# POWER.net
KiCad netlist of a schematic drawn in Altium Designer
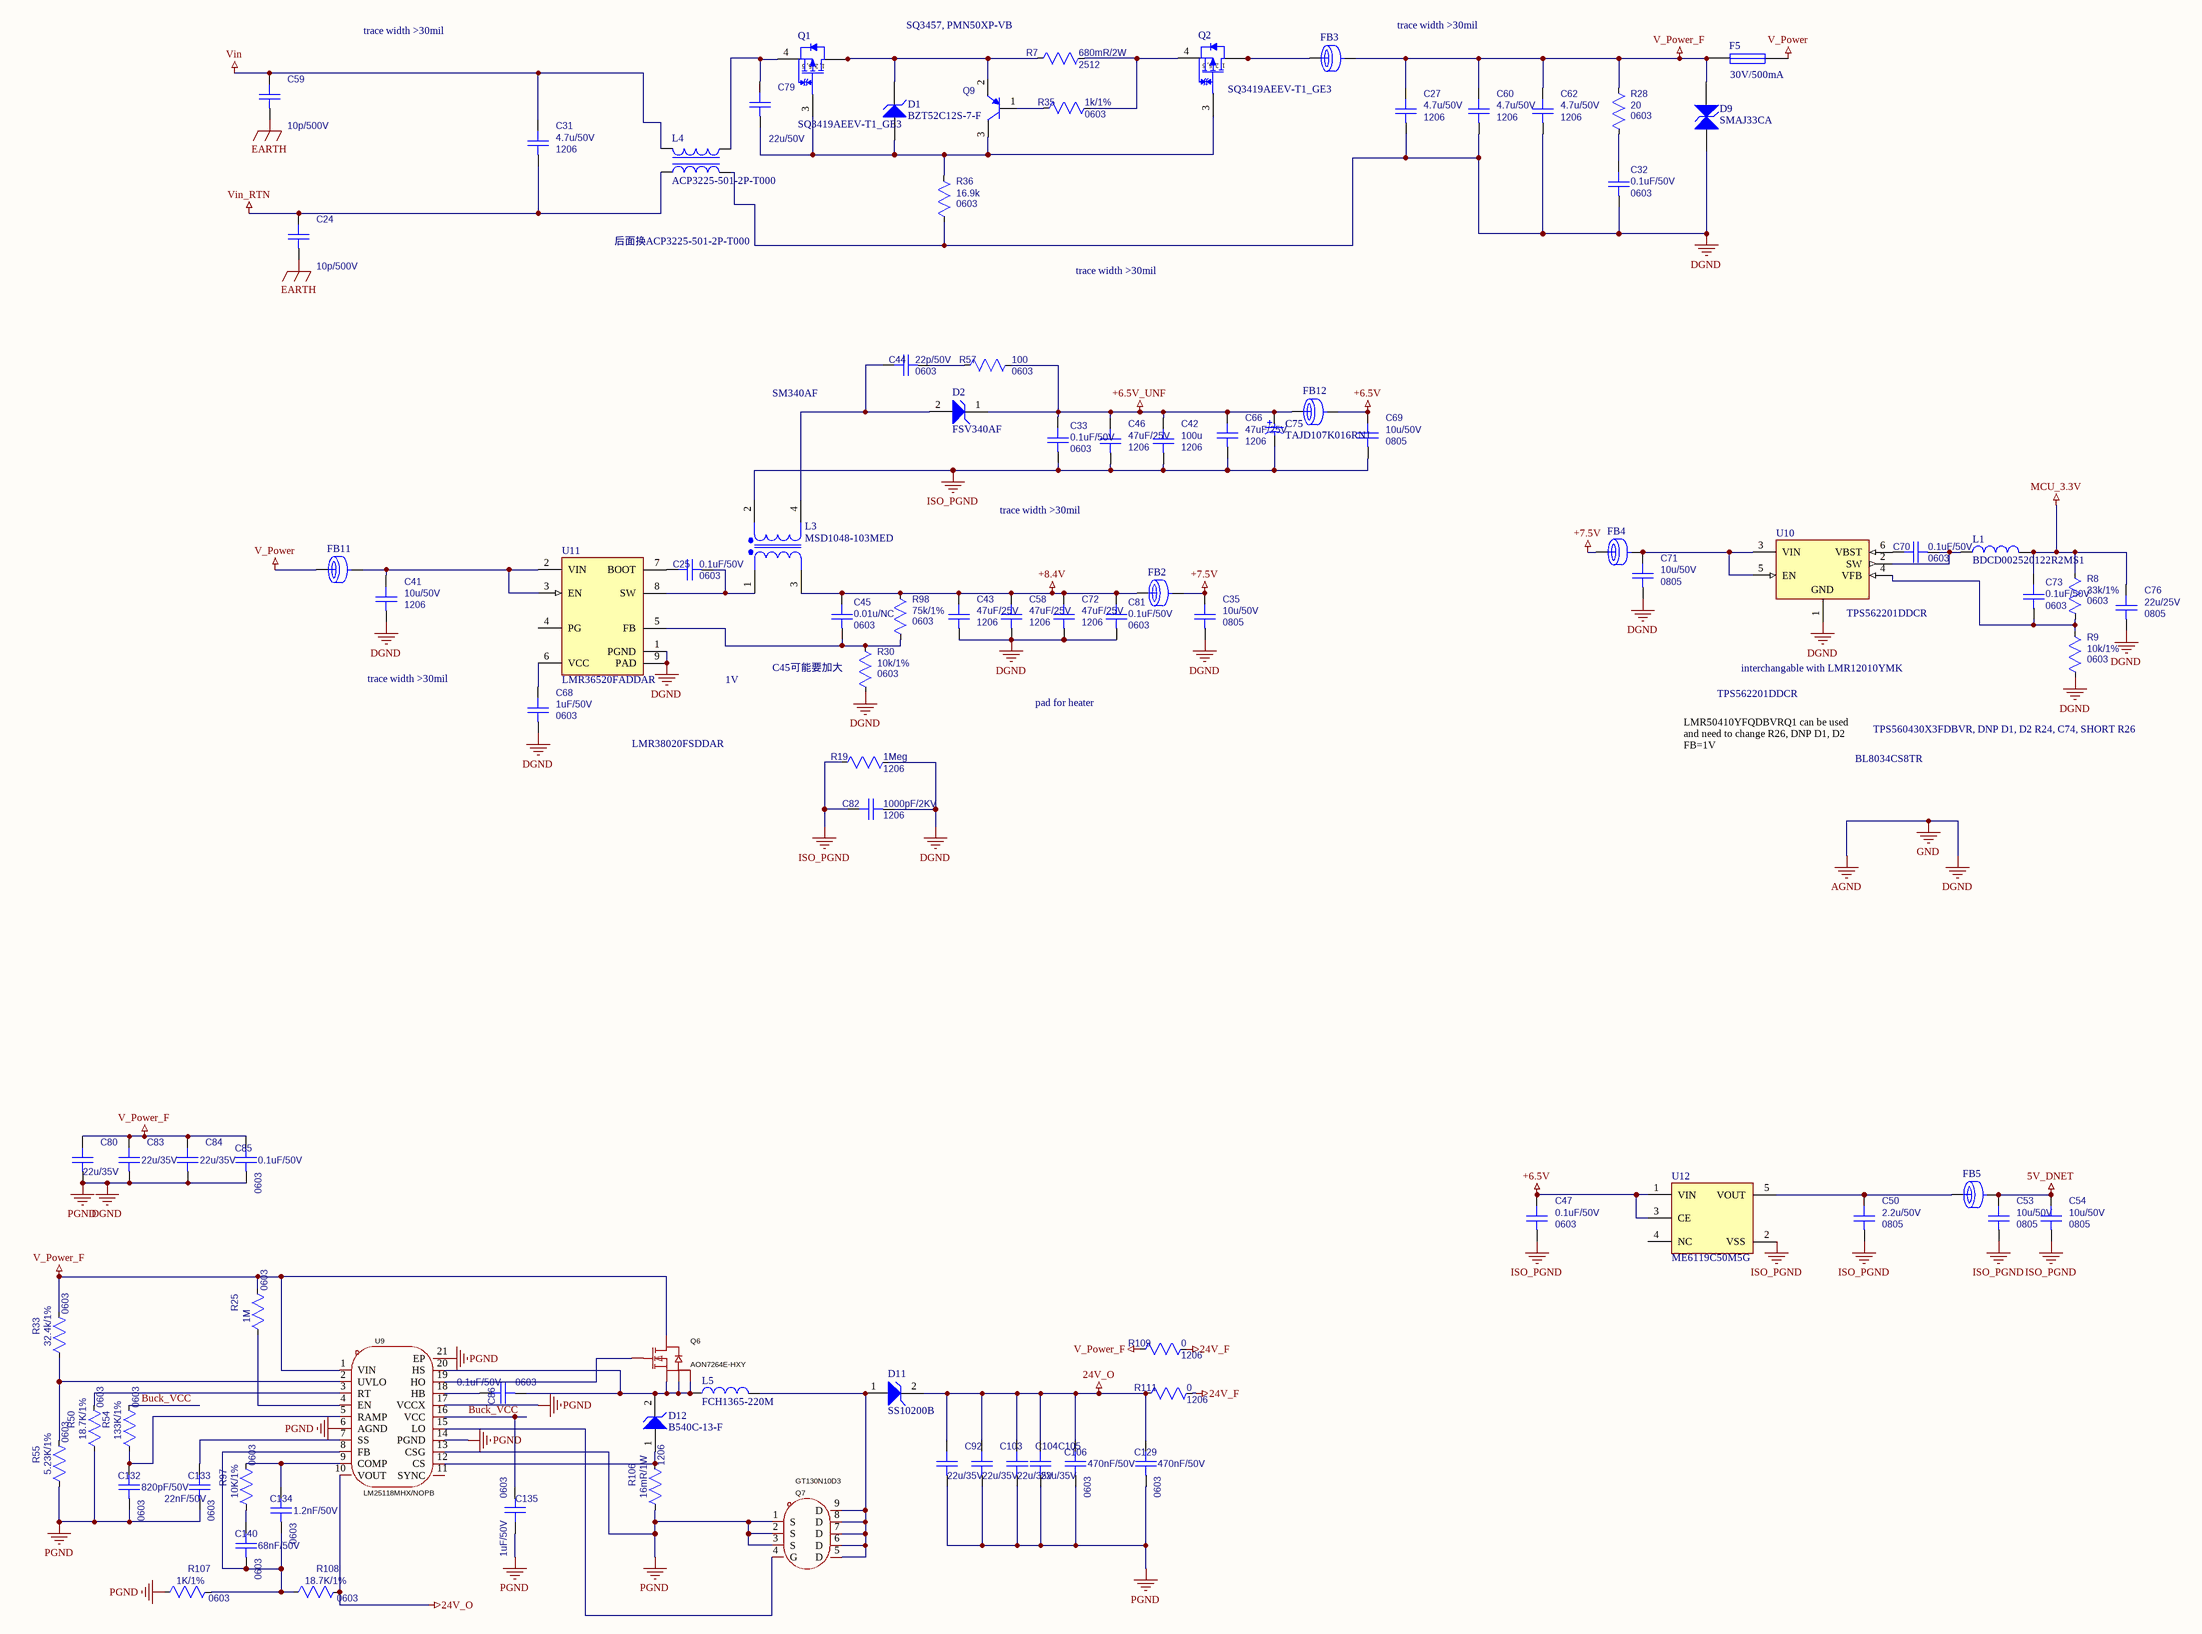
[diagram p0: POWER.SchDoc]

(export (version "E")
  (design (tool "Eeschema 10.0.6"))
  (components
    (comp (ref "C24")
      (value "10p/500V")
      (footprint "CAPC2012X127N_0805")
      (fields (field (name "PARTNUMBER") "CC0805JRNPOBBN100") (field (name "TOLERANCE") "[tol]"))
      (libsource (lib "Karl") (part "Capacitor_0805"))
    )
    (comp (ref "C25")
      (value "0.1uF/50V")
      (footprint "CAPC1608X092N_0603")
      (fields
        (field (name "PARTNUMBER") "CC0603KRX7R9BB104")
        (field (name "TOLERANCE") "[tol]")
        (field (name "PACKAGE") "0603")
      )
      (libsource (lib "Karl") (part "Capacitor_0603"))
    )
    (comp (ref "C27")
      (value "4.7u/50V")
      (footprint "CAPC3216X156N_1206")
      (fields
        (field (name "PARTNUMBER") "CL31B475KBHNNNE")
        (field (name "TOLERANCE") "[tol]")
        (field (name "PACKAGE") "1206")
      )
      (libsource (lib "Karl") (part "Capacitor_1206"))
    )
    (comp (ref "C31")
      (value "4.7u/50V")
      (footprint "CAPC3216X156N_1206")
      (fields
        (field (name "PARTNUMBER") "CL31B475KBHNNNE")
        (field (name "TOLERANCE") "[tol]")
        (field (name "PACKAGE") "1206")
      )
      (libsource (lib "Karl") (part "Capacitor_1206"))
    )
    (comp (ref "C32")
      (value "0.1uF/50V")
      (footprint "CAPC1608X092N_0603")
      (fields
        (field (name "PARTNUMBER") "CC0603KRX7R9BB104")
        (field (name "TOLERANCE") "[tol]")
        (field (name "PACKAGE") "0603")
      )
      (libsource (lib "Karl") (part "Capacitor_0603"))
    )
    (comp (ref "C33")
      (value "0.1uF/50V")
      (footprint "CAPC1608X092N_0603")
      (fields
        (field (name "PARTNUMBER") "CC0603KRX7R9BB104")
        (field (name "TOLERANCE") "[tol]")
        (field (name "PACKAGE") "0603")
      )
      (libsource (lib "Karl") (part "Capacitor_0603"))
    )
    (comp (ref "C35")
      (value "10u/50V")
      (footprint "CAPC2012X127N_0805")
      (fields
        (field (name "PARTNUMBER") "CL21A106KBYQNNE")
        (field (name "TOLERANCE") "[tol]")
        (field (name "PACKAGE") "0805")
      )
      (libsource (lib "Karl") (part "Capacitor_0805"))
    )
    (comp (ref "C41")
      (value "10u/50V")
      (footprint "CAPC3216X156N_1206")
      (fields
        (field (name "PARTNUMBER") "CL31A106KBHNNNE")
        (field (name "TOLERANCE") "[tol]")
        (field (name "PACKAGE") "1206")
      )
      (libsource (lib "Karl") (part "Capacitor_1206"))
    )
    (comp (ref "C42")
      (value "100u")
      (footprint "CAPC3216X156N_1206")
      (fields
        (field (name "PARTNUMBER") "GRM31CR61A107MEA8L")
        (field (name "TOLERANCE") "[tol]")
        (field (name "PACKAGE") "1206")
      )
      (libsource (lib "Karl") (part "Capacitor_1206"))
    )
    (comp (ref "C43")
      (value "47uF/25V")
      (footprint "CAPC3216X156N_1206")
      (fields
        (field (name "PARTNUMBER") "GRM31CR61E476ME44L")
        (field (name "TOLERANCE") "[tol]")
        (field (name "PACKAGE") "1206")
      )
      (libsource (lib "Karl") (part "Capacitor_1206"))
    )
    (comp (ref "C44")
      (value "22p/50V")
      (footprint "CAPC1608X092N_0603")
      (fields
        (field (name "PARTNUMBER") "C0603C220J1GACTU")
        (field (name "TOLERANCE") "[tol]")
        (field (name "PACKAGE") "0603")
      )
      (libsource (lib "Karl") (part "Capacitor_0603"))
    )
    (comp (ref "C45")
      (value "0.01u/NC")
      (footprint "CAPC1608X092N_0603")
      (fields
        (field (name "PARTNUMBER") "0603B103K500NT")
        (field (name "TOLERANCE") "[tol]")
        (field (name "PACKAGE") "0603")
        (field (name "Comment") "0.01uF/50V")
      )
      (libsource (lib "Karl") (part "Capacitor_0603"))
    )
    (comp (ref "C46")
      (value "47uF/25V")
      (footprint "CAPC3216X156N_1206")
      (fields
        (field (name "PARTNUMBER") "GRM31CR61E476ME44L")
        (field (name "TOLERANCE") "[tol]")
        (field (name "PACKAGE") "1206")
      )
      (libsource (lib "Karl") (part "Capacitor_1206"))
    )
    (comp (ref "C47")
      (value "0.1uF/50V")
      (footprint "CAPC1608X092N_0603")
      (fields
        (field (name "PARTNUMBER") "CC0603KRX7R9BB104")
        (field (name "TOLERANCE") "[tol]")
        (field (name "PACKAGE") "0603")
      )
      (libsource (lib "Karl") (part "Capacitor_0603"))
    )
    (comp (ref "C50")
      (value "2.2u/50V")
      (footprint "CAPC2012X127N_0805")
      (fields
        (field (name "PARTNUMBER") "CC0805KKX7R9BB225")
        (field (name "TOLERANCE") "[tol]")
        (field (name "PACKAGE") "0805")
      )
      (libsource (lib "Karl") (part "Capacitor_0805"))
    )
    (comp (ref "C53")
      (value "10u/50V")
      (footprint "CAPC2012X127N_0805")
      (fields
        (field (name "PARTNUMBER") "CL21A106KBYQNNE")
        (field (name "TOLERANCE") "[tol]")
        (field (name "PACKAGE") "0805")
      )
      (libsource (lib "Karl") (part "Capacitor_0805"))
    )
    (comp (ref "C54")
      (value "10u/50V")
      (footprint "CAPC2012X127N_0805")
      (fields
        (field (name "PARTNUMBER") "CL21A106KBYQNNE")
        (field (name "TOLERANCE") "[tol]")
        (field (name "PACKAGE") "0805")
      )
      (libsource (lib "Karl") (part "Capacitor_0805"))
    )
    (comp (ref "C58")
      (value "47uF/25V")
      (footprint "CAPC3216X156N_1206")
      (fields
        (field (name "PARTNUMBER") "GRM31CR61E476ME44L")
        (field (name "TOLERANCE") "[tol]")
        (field (name "PACKAGE") "1206")
      )
      (libsource (lib "Karl") (part "Capacitor_1206"))
    )
    (comp (ref "C59")
      (value "10p/500V")
      (footprint "CAPC2012X127N_0805")
      (fields (field (name "PARTNUMBER") "CC0805JRNPOBBN100") (field (name "TOLERANCE") "[tol]"))
      (libsource (lib "Karl") (part "Capacitor_0805"))
    )
    (comp (ref "C60")
      (value "4.7u/50V")
      (footprint "CAPC3216X156N_1206")
      (fields
        (field (name "PARTNUMBER") "CL31B475KBHNNNE")
        (field (name "TOLERANCE") "[tol]")
        (field (name "PACKAGE") "1206")
      )
      (libsource (lib "Karl") (part "Capacitor_1206"))
    )
    (comp (ref "C62")
      (value "4.7u/50V")
      (footprint "CAPC3216X156N_1206")
      (fields
        (field (name "PARTNUMBER") "CL31B475KBHNNNE")
        (field (name "TOLERANCE") "[tol]")
        (field (name "PACKAGE") "1206")
      )
      (libsource (lib "Karl") (part "Capacitor_1206"))
    )
    (comp (ref "C66")
      (value "47uF/25V")
      (footprint "CAPC3216X156N_1206")
      (fields
        (field (name "PARTNUMBER") "GRM31CR61E476ME44L")
        (field (name "TOLERANCE") "[tol]")
        (field (name "PACKAGE") "1206")
      )
      (libsource (lib "Karl") (part "Capacitor_1206"))
    )
    (comp (ref "C68")
      (value "1uF/50V")
      (footprint "CAPC1608X092N_0603")
      (fields
        (field (name "PARTNUMBER") "CL10A105KB8NNNC")
        (field (name "TOLERANCE") "[tol]")
        (field (name "PACKAGE") "0603")
      )
      (libsource (lib "Karl") (part "Capacitor_0603"))
    )
    (comp (ref "C69")
      (value "10u/50V")
      (footprint "CAPC2012X127N_0805")
      (fields
        (field (name "PARTNUMBER") "CL21A106KBYQNNE")
        (field (name "TOLERANCE") "[tol]")
        (field (name "PACKAGE") "0805")
      )
      (libsource (lib "Karl") (part "Capacitor_0805"))
    )
    (comp (ref "C70")
      (value "0.1uF/50V")
      (footprint "CAPC1608X092N_0603")
      (fields
        (field (name "PARTNUMBER") "CC0603KRX7R9BB104")
        (field (name "TOLERANCE") "[tol]")
        (field (name "PACKAGE") "0603")
      )
      (libsource (lib "Karl") (part "Capacitor_0603"))
    )
    (comp (ref "C71")
      (value "10u/50V")
      (footprint "CAPC2012X127N_0805")
      (fields
        (field (name "PARTNUMBER") "CL21A106KBYQNNE")
        (field (name "TOLERANCE") "[tol]")
        (field (name "PACKAGE") "0805")
      )
      (libsource (lib "Karl") (part "Capacitor_0805"))
    )
    (comp (ref "C72")
      (value "47uF/25V")
      (footprint "CAPC3216X156N_1206")
      (fields
        (field (name "PARTNUMBER") "GRM31CR61E476ME44L")
        (field (name "TOLERANCE") "[tol]")
        (field (name "PACKAGE") "1206")
      )
      (libsource (lib "Karl") (part "Capacitor_1206"))
    )
    (comp (ref "C73")
      (value "0.1uF/50V")
      (footprint "CAPC1608X092N_0603")
      (fields (field (name "TOLERANCE") "[tol]") (field (name "PACKAGE") "0603"))
      (libsource (lib "Karl") (part "Capacitor_0603"))
    )
    (comp (ref "C75")
      (value "TAJD107K016RNJ")
      (footprint "AVX-TAJ-D-2_L")
      (fields (field (name "TOLERANCE") "±10%") (field (name "PUBLISHER") "Bolgen Studio"))
      (libsource (lib "Bogen") (part "TAJD107K016RNJ"))
    )
    (comp (ref "C76")
      (value "22u/25V")
      (footprint "CAPC2012X127N_0805")
      (fields
        (field (name "PARTNUMBER") "CL21A226MAYNNNE")
        (field (name "TOLERANCE") "[tol]")
        (field (name "PACKAGE") "0805")
      )
      (libsource (lib "Karl") (part "Capacitor_0805"))
    )
    (comp (ref "C79")
      (value "22u/50V")
      (footprint "2220c")
      (description "Capacitor, MLCC")
      (fields (field (name "MANUFACTURER") "KEMET") (field (name "PARTNUMBER") "FS55X226K500EHG"))
      (libsource (lib "Karl") (part "Capacitor_1206"))
    )
    (comp (ref "C80")
      (value "22u/35V")
      (footprint "CAPC3216X156N_1206")
      (description "Capacitor, MLCC")
      (fields (field (name "MANUFACTURER") "KEMET") (field (name "PARTNUMBER") "C3216X5R1V226MTJ00E"))
      (libsource (lib "Karl") (part "Capacitor_1206"))
    )
    (comp (ref "C81")
      (value "0.1uF/50V")
      (footprint "CAPC1608X092N_0603")
      (fields
        (field (name "PARTNUMBER") "CC0603KRX7R9BB104")
        (field (name "TOLERANCE") "[tol]")
        (field (name "PACKAGE") "0603")
      )
      (libsource (lib "Karl") (part "Capacitor_0603"))
    )
    (comp (ref "C82")
      (value "1000pF/2KV")
      (footprint "CAPC3216X156N_1206")
      (fields
        (field (name "PARTNUMBER") "CC1206KKX7RDBB102")
        (field (name "TOLERANCE") "[tol]")
        (field (name "PACKAGE") "1206")
      )
      (libsource (lib "Karl") (part "Capacitor_1206"))
    )
    (comp (ref "C83")
      (value "22u/35V")
      (footprint "CAPC3216X156N_1206")
      (description "Capacitor, MLCC")
      (fields (field (name "MANUFACTURER") "KEMET") (field (name "PARTNUMBER") "C3216X5R1V226MTJ00E"))
      (libsource (lib "Karl") (part "Capacitor_1206"))
    )
    (comp (ref "C84")
      (value "22u/35V")
      (footprint "CAPC3216X156N_1206")
      (description "Capacitor, MLCC")
      (fields (field (name "MANUFACTURER") "KEMET") (field (name "PARTNUMBER") "C3216X5R1V226MTJ00E"))
      (libsource (lib "Karl") (part "Capacitor_1206"))
    )
    (comp (ref "C85")
      (value "0.1uF/50V")
      (footprint "CAPC1608X092N_0603")
      (description "Capacitor, MLCC")
      (fields
        (field (name "MANUFACTURER") "KEMET")
        (field (name "PARTNUMBER") "CC0603KRX7R9BB104")
        (field (name "PACKAGE") "0603")
      )
      (libsource (lib "Karl") (part "Capacitor_0603"))
    )
    (comp (ref "C86")
      (value "0.1uF/50V")
      (footprint "CAPC1608X092N_0603")
      (description "Capacitor, MLCC")
      (fields
        (field (name "MANUFACTURER") "KEMET")
        (field (name "PARTNUMBER") "CC0603KRX7R9BB104")
        (field (name "PACKAGE") "0603")
      )
      (libsource (lib "Karl") (part "Capacitor_0603"))
    )
    (comp (ref "C92")
      (value "22u/35V")
      (footprint "CAPC3216X156N_1206")
      (description "Capacitor, MLCC")
      (fields (field (name "MANUFACTURER") "KEMET") (field (name "PARTNUMBER") "C3216X5R1V226MTJ00E"))
      (libsource (lib "Karl") (part "Capacitor_1206"))
    )
    (comp (ref "C103")
      (value "22u/35V")
      (footprint "CAPC3216X156N_1206")
      (description "Capacitor, MLCC")
      (fields (field (name "MANUFACTURER") "KEMET") (field (name "PARTNUMBER") "C3216X5R1V226MTJ00E"))
      (libsource (lib "Karl") (part "Capacitor_1206"))
    )
    (comp (ref "C104")
      (value "22u/35V")
      (footprint "CAPC3216X156N_1206")
      (description "Capacitor, MLCC")
      (fields (field (name "MANUFACTURER") "KEMET") (field (name "PARTNUMBER") "C3216X5R1V226MTJ00E"))
      (libsource (lib "Karl") (part "Capacitor_1206"))
    )
    (comp (ref "C105")
      (value "22u/35V")
      (footprint "CAPC3216X156N_1206")
      (description "Capacitor, MLCC")
      (fields (field (name "MANUFACTURER") "KEMET") (field (name "PARTNUMBER") "C3216X5R1V226MTJ00E"))
      (libsource (lib "Karl") (part "Capacitor_1206"))
    )
    (comp (ref "C106")
      (value "470nF/50V")
      (footprint "CAPC1608X092N_0603")
      (description "Capacitor, MLCC")
      (fields (field (name "MANUFACTURER") "KEMET") (field (name "PACKAGE") "0603"))
      (libsource (lib "Karl") (part "Capacitor_0603"))
    )
    (comp (ref "C129")
      (value "470nF/50V")
      (footprint "CAPC1608X092N_0603")
      (description "Capacitor, MLCC")
      (fields (field (name "MANUFACTURER") "KEMET") (field (name "PACKAGE") "0603"))
      (libsource (lib "Karl") (part "Capacitor_0603"))
    )
    (comp (ref "C132")
      (value "820pF/50V")
      (footprint "CAPC1608X092N_0603")
      (description "Capacitor, MLCC")
      (fields (field (name "MANUFACTURER") "KEMET") (field (name "PACKAGE") "0603"))
      (libsource (lib "Karl") (part "Capacitor_0603"))
    )
    (comp (ref "C133")
      (value "22nF/50V")
      (footprint "CAPC1608X092N_0603")
      (description "Capacitor, MLCC")
      (fields (field (name "MANUFACTURER") "KEMET") (field (name "PACKAGE") "0603"))
      (libsource (lib "Karl") (part "Capacitor_0603"))
    )
    (comp (ref "C134")
      (value "1.2nF/50V")
      (footprint "CAPC1608X092N_0603")
      (description "Capacitor, MLCC")
      (fields (field (name "MANUFACTURER") "KEMET") (field (name "PACKAGE") "0603"))
      (libsource (lib "Karl") (part "Capacitor_0603"))
    )
    (comp (ref "C135")
      (value "1uF/50V")
      (footprint "CAPC1608X092N_0603")
      (description "Capacitor, MLCC")
      (fields
        (field (name "MANUFACTURER") "KEMET")
        (field (name "PARTNUMBER") "CL10A105KB8NNNC")
        (field (name "PACKAGE") "0603")
      )
      (libsource (lib "Karl") (part "Capacitor_0603"))
    )
    (comp (ref "C140")
      (value "68nF/50V")
      (footprint "CAPC1608X092N_0603")
      (description "Capacitor, MLCC")
      (fields (field (name "MANUFACTURER") "KEMET") (field (name "PACKAGE") "0603"))
      (libsource (lib "Karl") (part "Capacitor_0603"))
    )
    (comp (ref "D1")
      (value "BZT52C12S-7-F")
      (footprint "DIOD-SOD323-2_V")
      (fields (field (name "PARTNUMBER") "BZT52C12S"))
      (libsource (lib "Bogen") (part "BZT52C12S-7-F"))
    )
    (comp (ref "D2")
      (value "FSV340AF")
      (footprint "ONSC-SMA-FL-2-403AD_V")
      (fields (field (name "PARTNUMBER") "SM340AF"))
      (libsource (lib "") (part "FSV340AF_1"))
    )
    (comp (ref "D9")
      (value "SMAJ33CA")
      (footprint "LFUS-DO-214AC-A-2_N")
      (libsource (lib "Bogen") (part "SMAJ12CA"))
    )
    (comp (ref "D11")
      (value "SS10200B")
      (footprint "SMB")
      (description "Schottky Barrier Rectifier, 40 V, 2-Pin SMA-FL, Pb-Free, Tape and Reel")
      (fields (field (name "MANUFACTURER") "On Semiconductor"))
      (libsource (lib "Bogen") (part "FSV340AF"))
    )
    (comp (ref "D12")
      (value "B540C-13-F")
      (footprint "SMC")
      (description "Schottky Barrier Rectifier, 40 V, 2-Pin SMA-FL, Pb-Free, Tape and Reel")
      (fields (field (name "MANUFACTURER") "On Semiconductor"))
      (libsource (lib "Bogen") (part "FSV340AF"))
    )
    (comp (ref "F5")
      (value "30V/500mA")
      (footprint "RESC3216X070N_1206")
      (fields (field (name "PARTNUMBER") "BSMD1206-050-30V") (field (name "PUBLISHER") "Altium Limited"))
      (libsource (lib "Miscellaneous Devices") (part "Fuse 1"))
    )
    (comp (ref "FB2")
      (value "FBC0603")
      (footprint "FBC0603")
      (fields (field (name "PARTNUMBER") "BLM18AG601SN1D"))
      (libsource (lib "Karl") (part "FBC0603"))
    )
    (comp (ref "FB3")
      (value "BLM31PG121SN1L")
      (footprint "RESC3216X070N_1206")
      (libsource (lib "Karl") (part "FBC0603"))
    )
    (comp (ref "FB4")
      (value "FBC0603")
      (footprint "FBC0603")
      (fields (field (name "PARTNUMBER") "BLM18AG601SN1D"))
      (libsource (lib "Karl") (part "FBC0603"))
    )
    (comp (ref "FB5")
      (value "FBC0603")
      (footprint "FBC0603")
      (fields (field (name "PARTNUMBER") "BLM18AG601SN1D"))
      (libsource (lib "Karl") (part "FBC0603"))
    )
    (comp (ref "FB11")
      (value "FBC0603")
      (footprint "FBC0603")
      (fields (field (name "PARTNUMBER") "BLM18AG601SN1D"))
      (libsource (lib "Karl") (part "FBC0603"))
    )
    (comp (ref "FB12")
      (value "FBC0603")
      (footprint "FBC0603")
      (fields (field (name "PARTNUMBER") "BLM18AG601SN1D"))
      (libsource (lib "Karl") (part "FBC0603"))
    )
    (comp (ref "L1")
      (value "BDCD002520122R2MS1")
      (footprint "PULS-BDCD00252012_V")
      (fields (field (name "TOLERANCE") "±20%"))
      (libsource (lib "Bogen") (part "BDCD002520122R2MS1"))
    )
    (comp (ref "L3")
      (value "MSD1048-103MED")
      (footprint "COIL-MSD1048-4_V")
      (fields (field (name "TOLERANCE") "+/- 10%"))
      (libsource (lib "Bogen") (part "MSD1048-103MED"))
    )
    (comp (ref "L4")
      (value "ACP3225-501-2P-T000")
      (footprint "TDK-ACP3225-4_V")
      (fields (field (name "PARTNUMBER") "AD8615AUJZ-R2"))
      (libsource (lib "Bogen") (part "ACP3225-501-2P-T000"))
    )
    (comp (ref "L5")
      (value "FCH1365-220M")
      (footprint "Bogen:FNGCH-FCH1365-2_V")
      (fields (field (name "MANUFACTURER") "CJiang Technology"))
      (libsource (lib "Bogen") (part "FXL0630-100-M"))
    )
    (comp (ref "Q1")
      (value "SQ3419AEEV-T1_GE3")
      (footprint "VISH-TSOP-6_V")
      (fields (field (name "PARTNUMBER") "PMN50XP-VB"))
      (libsource (lib "Bogen") (part "SQ3419AEEV-T1_GE3"))
    )
    (comp (ref "Q2")
      (value "SQ3419AEEV-T1_GE3")
      (footprint "VISH-TSOP-6_V")
      (fields (field (name "PARTNUMBER") "PMN50XP-VB"))
      (libsource (lib "Bogen") (part "SQ3419AEEV-T1_GE3"))
    )
    (comp (ref "Q6")
      (value "AON7264E-HXY")
      (footprint "WDFN-5_L3.3-W3.3-P0.65-BL")
      (fields (field (name "MANUFACTURER") "HXY MOSFET(华轩阳电子)"))
      (libsource (lib "altium-import") (part "root_0_AON7264E-HXY_"))
    )
    (comp (ref "Q7")
      (value "GT130N10D3")
      (footprint "PPAK3X3_L3.2-W3.1-P0.65-LS3.3-BL")
      (fields (field (name "MANUFACTURER") "GOFORD(谷峰)"))
      (libsource (lib "altium-import") (part "root_0_GT700P08D3_"))
    )
    (comp (ref "Q9")
      (value "MMBT4403-7-F")
      (footprint "SOT-23_3N_95P_240x300x100")
      (libsource (lib "Karl") (part "OEM_Diodes_MMBT4403"))
    )
    (comp (ref "R7")
      (value "680mR/2W")
      (footprint "RESC6331X070N_2512")
      (fields (field (name "TOLERANCE") "tol") (field (name "PACKAGE") "2512"))
      (libsource (lib "Karl") (part "Resistor_2512"))
    )
    (comp (ref "R8")
      (value "33k/1%")
      (footprint "RESC1608X055N_0603")
      (fields
        (field (name "PARTNUMBER") "RC0603FR-0733KL")
        (field (name "TOLERANCE") "tol")
        (field (name "PACKAGE") "0603")
      )
      (libsource (lib "Karl") (part "Resistor_0603"))
    )
    (comp (ref "R9")
      (value "10k/1%")
      (footprint "RESC1608X055N_0603")
      (fields
        (field (name "PARTNUMBER") "RC0603FR-0710KL")
        (field (name "TOLERANCE") "tol")
        (field (name "PACKAGE") "0603")
      )
      (libsource (lib "Karl") (part "Resistor_0603"))
    )
    (comp (ref "R19")
      (value "1Meg")
      (footprint "RESC3216X070N_1206")
      (fields
        (field (name "PARTNUMBER") "RC1206FR-071ML")
        (field (name "TOLERANCE") "tol")
        (field (name "PACKAGE") "1206")
      )
      (libsource (lib "Karl") (part "Resistor_1206"))
    )
    (comp (ref "R25")
      (value "1M")
      (footprint "RESC1608X055N_0603")
      (description "Resistor, Standard")
      (fields (field (name "MANUFACTURER") "Yageo") (field (name "PACKAGE") "0603"))
      (libsource (lib "Karl") (part "Resistor_0603"))
    )
    (comp (ref "R28")
      (value "20")
      (footprint "RESC1608X055N_0603")
      (fields
        (field (name "PARTNUMBER") "RK73H1JTTD16R0F")
        (field (name "TOLERANCE") "tol")
        (field (name "PACKAGE") "0603")
      )
      (libsource (lib "Karl") (part "Resistor_0603"))
    )
    (comp (ref "R30")
      (value "10k/1%")
      (footprint "RESC1608X055N_0603")
      (fields
        (field (name "PARTNUMBER") "RC0603FR-0710KL")
        (field (name "TOLERANCE") "tol")
        (field (name "PACKAGE") "0603")
      )
      (libsource (lib "Karl") (part "Resistor_0603"))
    )
    (comp (ref "R33")
      (value "32.4k/1%")
      (footprint "RESC1608X055N_0603")
      (description "Resistor, Standard")
      (fields (field (name "MANUFACTURER") "Yageo") (field (name "PACKAGE") "0603"))
      (libsource (lib "Karl") (part "Resistor_0603"))
    )
    (comp (ref "R35")
      (value "1k/1%")
      (footprint "RESC1608X055N_0603")
      (fields
        (field (name "PARTNUMBER") "RC0603FR-071KL")
        (field (name "TOLERANCE") "tol")
        (field (name "PACKAGE") "0603")
      )
      (libsource (lib "Karl") (part "Resistor_0603"))
    )
    (comp (ref "R36")
      (value "16.9k")
      (footprint "RESC1608X055N_0603")
      (fields
        (field (name "PARTNUMBER") "FRC0603F1692TS")
        (field (name "TOLERANCE") "tol")
        (field (name "PACKAGE") "0603")
      )
      (libsource (lib "Karl") (part "Resistor_0603"))
    )
    (comp (ref "R50")
      (value "18.7K/1%")
      (footprint "RESC1608X055N_0603")
      (description "Resistor, Standard")
      (fields (field (name "MANUFACTURER") "Yageo") (field (name "PACKAGE") "0603"))
      (libsource (lib "Karl") (part "Resistor_0603"))
    )
    (comp (ref "R54")
      (value "133K/1%")
      (footprint "RESC1608X055N_0603")
      (description "Resistor, Standard")
      (fields (field (name "MANUFACTURER") "Yageo") (field (name "PACKAGE") "0603"))
      (libsource (lib "Karl") (part "Resistor_0603"))
    )
    (comp (ref "R55")
      (value "5.23K/1%")
      (footprint "RESC1608X055N_0603")
      (description "Resistor, Standard")
      (fields (field (name "MANUFACTURER") "Yageo") (field (name "PACKAGE") "0603"))
      (libsource (lib "Karl") (part "Resistor_0603"))
    )
    (comp (ref "R57")
      (value "100")
      (footprint "RESC1608X055N_0603")
      (fields
        (field (name "PARTNUMBER") "RT0603BRD07100RL")
        (field (name "TOLERANCE") "tol")
        (field (name "PACKAGE") "0603")
      )
      (libsource (lib "Karl") (part "Resistor_0603"))
    )
    (comp (ref "R97")
      (value "10K/1%")
      (footprint "RESC1608X055N_0603")
      (description "Resistor, Standard")
      (fields
        (field (name "MANUFACTURER") "Yageo")
        (field (name "PARTNUMBER") "RC0603FR-0710KL")
        (field (name "PACKAGE") "0603")
      )
      (libsource (lib "Karl") (part "Resistor_0603"))
    )
    (comp (ref "R98")
      (value "75k/1%")
      (footprint "RESC1608X055N_0603")
      (fields
        (field (name "PARTNUMBER") "0603WAF7502T5E")
        (field (name "TOLERANCE") "tol")
        (field (name "PACKAGE") "0603")
      )
      (libsource (lib "Karl") (part "Resistor_0603"))
    )
    (comp (ref "R106")
      (value "16mR/1W")
      (footprint "RESC3216X070N_1206")
      (description "Resistor, Standard")
      (fields (field (name "MANUFACTURER") "Yageo") (field (name "PACKAGE") "1206"))
      (libsource (lib "Karl") (part "Resistor_0603"))
    )
    (comp (ref "R107")
      (value "1K/1%")
      (footprint "RESC1608X055N_0603")
      (description "Resistor, Standard")
      (fields
        (field (name "MANUFACTURER") "Yageo")
        (field (name "PARTNUMBER") "RC0603FR-071KL")
        (field (name "PACKAGE") "0603")
      )
      (libsource (lib "Karl") (part "Resistor_0603"))
    )
    (comp (ref "R108")
      (value "18.7K/1%")
      (footprint "RESC1608X055N_0603")
      (description "Resistor, Standard")
      (fields (field (name "MANUFACTURER") "Yageo") (field (name "PACKAGE") "0603"))
      (libsource (lib "Karl") (part "Resistor_0603"))
    )
    (comp (ref "R109")
      (value "0")
      (footprint "RESC3216X070N_1206")
      (fields (field (name "TOLERANCE") "tol") (field (name "PACKAGE") "1206"))
      (libsource (lib "Karl") (part "Resistor_2512"))
    )
    (comp (ref "R111")
      (value "0")
      (footprint "RESC3216X070N_1206")
      (fields (field (name "TOLERANCE") "tol") (field (name "PACKAGE") "1206"))
      (libsource (lib "Karl") (part "Resistor_2512"))
    )
    (comp (ref "U9")
      (value "LM25118MHX/NOPB")
      (footprint "HTSSOP-20_L6.5-W4.4-P0.65-LS6.4-BL-EP")
      (fields (field (name "MANUFACTURER") "TI(德州仪器)"))
      (libsource (lib "altium-import") (part "root_0_LM25118MHX/NOPB_"))
    )
    (comp (ref "U10")
      (value "TPS562201DDCR")
      (footprint "DDC0006A_L")
      (libsource (lib "Bogen") (part "TPS562201DDCR"))
    )
    (comp (ref "U11")
      (value "LMR36520FADDAR")
      (footprint "DDA0008A_M")
      (fields (field (name "PUBLISHER") "Bolgen Studio"))
      (libsource (lib "Bogen") (part "LMR36520FADDAR"))
    )
    (comp (ref "U12")
      (value "ME6119C50M5G")
      (footprint "MCRN-SOT23-5_V")
      (libsource (lib "Bogen") (part "ME6119C50M5G"))
    )
  )
  (nets
    (net (code "1") (name "+6.5V") (class "Default")
      (node (ref "C47") (pin "1") (pinfunction "1_1") (pintype "passive"))
      (node (ref "C69") (pin "1") (pinfunction "1_1") (pintype "passive"))
      (node (ref "FB12") (pin "2") (pinfunction "2_2") (pintype "passive"))
      (node (ref "U12") (pin "1") (pinfunction "VIN_1") (pintype "passive"))
      (node (ref "U12") (pin "3") (pinfunction "CE_3") (pintype "passive"))
    )
    (net (code "2") (name "+6.5V_UNF") (class "Default")
      (node (ref "C33") (pin "1") (pinfunction "1_1") (pintype "passive"))
      (node (ref "C42") (pin "1") (pinfunction "1_1") (pintype "passive"))
      (node (ref "C46") (pin "1") (pinfunction "1_1") (pintype "passive"))
      (node (ref "C66") (pin "1") (pinfunction "1_1") (pintype "passive"))
      (node (ref "C75") (pin "1") (pinfunction "1_1") (pintype "passive"))
      (node (ref "D2") (pin "1") (pinfunction "K_1") (pintype "passive"))
      (node (ref "FB12") (pin "1") (pinfunction "1_1") (pintype "passive"))
      (node (ref "R57") (pin "1") (pinfunction "1_1") (pintype "passive"))
    )
    (net (code "3") (name "+7.5V") (class "Default")
      (node (ref "C35") (pin "1") (pinfunction "1_1") (pintype "passive"))
      (node (ref "FB2") (pin "2") (pinfunction "2_2") (pintype "passive"))
      (node (ref "FB4") (pin "1") (pinfunction "1_1") (pintype "passive"))
    )
    (net (code "4") (name "+8.4V") (class "Default")
      (node (ref "C43") (pin "1") (pinfunction "1_1") (pintype "passive"))
      (node (ref "C45") (pin "1") (pinfunction "1_1") (pintype "passive"))
      (node (ref "C58") (pin "1") (pinfunction "1_1") (pintype "passive"))
      (node (ref "C72") (pin "1") (pinfunction "1_1") (pintype "passive"))
      (node (ref "C81") (pin "1") (pinfunction "1_1") (pintype "passive"))
      (node (ref "FB2") (pin "1") (pinfunction "1_1") (pintype "passive"))
      (node (ref "L3") (pin "3") (pinfunction "3_3") (pintype "passive"))
      (node (ref "R98") (pin "2") (pinfunction "2_2") (pintype "passive"))
    )
    (net (code "5") (name "/Buck_VCC") (class "Default")
      (node (ref "C135") (pin "2") (pinfunction "2_2") (pintype "passive"))
      (node (ref "R54") (pin "1") (pinfunction "1_1") (pintype "passive"))
      (node (ref "U9") (pin "16") (pinfunction "VCC_16") (pintype "passive"))
    )
    (net (code "6") (name "5V_DNET") (class "Default")
      (node (ref "C53") (pin "1") (pinfunction "1_1") (pintype "passive"))
      (node (ref "C54") (pin "1") (pinfunction "1_1") (pintype "passive"))
      (node (ref "FB5") (pin "2") (pinfunction "2_2") (pintype "passive"))
    )
    (net (code "7") (name "24V_F") (class "Default")
      (node (ref "R109") (pin "1") (pinfunction "1_1") (pintype "passive"))
      (node (ref "R111") (pin "1") (pinfunction "1_1") (pintype "passive"))
    )
    (net (code "8") (name "24V_O") (class "Default")
      (node (ref "C103") (pin "1") (pinfunction "1_1") (pintype "passive"))
      (node (ref "C104") (pin "1") (pinfunction "1_1") (pintype "passive"))
      (node (ref "C105") (pin "1") (pinfunction "1_1") (pintype "passive"))
      (node (ref "C106") (pin "1") (pinfunction "1_1") (pintype "passive"))
      (node (ref "C129") (pin "1") (pinfunction "1_1") (pintype "passive"))
      (node (ref "C92") (pin "1") (pinfunction "1_1") (pintype "passive"))
      (node (ref "D11") (pin "2") (pinfunction "K_2") (pintype "passive"))
      (node (ref "R108") (pin "1") (pinfunction "1_1") (pintype "passive"))
      (node (ref "R111") (pin "2") (pinfunction "2_2") (pintype "passive"))
      (node (ref "U9") (pin "10") (pinfunction "VOUT_10") (pintype "passive"))
    )
    (net (code "9") (name "AGND") (class "Default")
      (node (ref "C103") (pin "2") (pinfunction "2_2") (pintype "passive"))
      (node (ref "C104") (pin "2") (pinfunction "2_2") (pintype "passive"))
      (node (ref "C105") (pin "2") (pinfunction "2_2") (pintype "passive"))
      (node (ref "C106") (pin "2") (pinfunction "2_2") (pintype "passive"))
      (node (ref "C129") (pin "2") (pinfunction "2_2") (pintype "passive"))
      (node (ref "C132") (pin "2") (pinfunction "2_2") (pintype "passive"))
      (node (ref "C133") (pin "2") (pinfunction "2_2") (pintype "passive"))
      (node (ref "C135") (pin "1") (pinfunction "1_1") (pintype "passive"))
      (node (ref "C27") (pin "2") (pinfunction "2_2") (pintype "passive"))
      (node (ref "C32") (pin "2") (pinfunction "2_2") (pintype "passive"))
      (node (ref "C35") (pin "2") (pinfunction "2_2") (pintype "passive"))
      (node (ref "C41") (pin "2") (pinfunction "2_2") (pintype "passive"))
      (node (ref "C43") (pin "2") (pinfunction "2_2") (pintype "passive"))
      (node (ref "C58") (pin "2") (pinfunction "2_2") (pintype "passive"))
      (node (ref "C60") (pin "2") (pinfunction "2_2") (pintype "passive"))
      (node (ref "C62") (pin "2") (pinfunction "2_2") (pintype "passive"))
      (node (ref "C68") (pin "2") (pinfunction "2_2") (pintype "passive"))
      (node (ref "C71") (pin "2") (pinfunction "2_2") (pintype "passive"))
      (node (ref "C72") (pin "2") (pinfunction "2_2") (pintype "passive"))
      (node (ref "C76") (pin "2") (pinfunction "2_2") (pintype "passive"))
      (node (ref "C80") (pin "2") (pinfunction "2_2") (pintype "passive"))
      (node (ref "C81") (pin "2") (pinfunction "2_2") (pintype "passive"))
      (node (ref "C82") (pin "2") (pinfunction "2_2") (pintype "passive"))
      (node (ref "C83") (pin "2") (pinfunction "2_2") (pintype "passive"))
      (node (ref "C84") (pin "2") (pinfunction "2_2") (pintype "passive"))
      (node (ref "C85") (pin "2") (pinfunction "2_2") (pintype "passive"))
      (node (ref "C92") (pin "2") (pinfunction "2_2") (pintype "passive"))
      (node (ref "D9") (pin "1") (pinfunction "A_1") (pintype "passive"))
      (node (ref "L4") (pin "3") (pinfunction "3_3") (pintype "passive"))
      (node (ref "Q7") (pin "1") (pinfunction "S_1") (pintype "passive"))
      (node (ref "Q7") (pin "2") (pinfunction "S_2") (pintype "passive"))
      (node (ref "Q7") (pin "3") (pinfunction "S_3") (pintype "passive"))
      (node (ref "R106") (pin "2") (pinfunction "2_2") (pintype "passive"))
      (node (ref "R107") (pin "2") (pinfunction "2_2") (pintype "passive"))
      (node (ref "R19") (pin "1") (pinfunction "1_1") (pintype "passive"))
      (node (ref "R30") (pin "1") (pinfunction "1_1") (pintype "passive"))
      (node (ref "R36") (pin "1") (pinfunction "1_1") (pintype "passive"))
      (node (ref "R50") (pin "2") (pinfunction "2_2") (pintype "passive"))
      (node (ref "R55") (pin "2") (pinfunction "2_2") (pintype "passive"))
      (node (ref "R9") (pin "1") (pinfunction "1_1") (pintype "passive"))
      (node (ref "U10") (pin "1") (pinfunction "GND_1") (pintype "power_in"))
      (node (ref "U11") (pin "1") (pinfunction "PGND_1") (pintype "passive"))
      (node (ref "U11") (pin "9") (pinfunction "PAD_9") (pintype "passive"))
      (node (ref "U9") (pin "13") (pinfunction "CSG_13") (pintype "passive"))
      (node (ref "U9") (pin "14") (pinfunction "PGND_14") (pintype "passive"))
      (node (ref "U9") (pin "17") (pinfunction "VCCX_17") (pintype "passive"))
      (node (ref "U9") (pin "21") (pinfunction "EP_21") (pintype "passive"))
      (node (ref "U9") (pin "6") (pinfunction "AGND_6") (pintype "passive"))
    )
    (net (code "10") (name "EARTH") (class "Default")
      (node (ref "C24") (pin "2") (pinfunction "2_2") (pintype "passive"))
      (node (ref "C59") (pin "2") (pinfunction "2_2") (pintype "passive"))
    )
    (net (code "11") (name "ISO_PGND") (class "Default")
      (node (ref "C33") (pin "2") (pinfunction "2_2") (pintype "passive"))
      (node (ref "C42") (pin "2") (pinfunction "2_2") (pintype "passive"))
      (node (ref "C46") (pin "2") (pinfunction "2_2") (pintype "passive"))
      (node (ref "C47") (pin "2") (pinfunction "2_2") (pintype "passive"))
      (node (ref "C50") (pin "2") (pinfunction "2_2") (pintype "passive"))
      (node (ref "C53") (pin "2") (pinfunction "2_2") (pintype "passive"))
      (node (ref "C54") (pin "2") (pinfunction "2_2") (pintype "passive"))
      (node (ref "C66") (pin "2") (pinfunction "2_2") (pintype "passive"))
      (node (ref "C69") (pin "2") (pinfunction "2_2") (pintype "passive"))
      (node (ref "C75") (pin "2") (pinfunction "2_2") (pintype "passive"))
      (node (ref "C82") (pin "1") (pinfunction "1_1") (pintype "passive"))
      (node (ref "L3") (pin "2") (pinfunction "2_2") (pintype "passive"))
      (node (ref "R19") (pin "2") (pinfunction "2_2") (pintype "passive"))
      (node (ref "U12") (pin "2") (pinfunction "VSS_2") (pintype "passive"))
    )
    (net (code "12") (name "MCU_3.3V") (class "Default")
      (node (ref "C73") (pin "1") (pinfunction "1_1") (pintype "passive"))
      (node (ref "C76") (pin "1") (pinfunction "1_1") (pintype "passive"))
      (node (ref "L1") (pin "2") (pinfunction "2_2") (pintype "passive"))
      (node (ref "R8") (pin "2") (pinfunction "2_2") (pintype "passive"))
    )
    (net (code "13") (name "Net-(C32-Pad1)") (class "Default")
      (node (ref "C32") (pin "1") (pinfunction "1_1") (pintype "passive"))
      (node (ref "R28") (pin "1") (pinfunction "1_1") (pintype "passive"))
    )
    (net (code "14") (name "Net-(C44-Pad2)") (class "Default")
      (node (ref "C44") (pin "2") (pinfunction "2_2") (pintype "passive"))
      (node (ref "R57") (pin "2") (pinfunction "2_2") (pintype "passive"))
    )
    (net (code "15") (name "Net-(C140-Pad1)") (class "Default")
      (node (ref "C140") (pin "1") (pinfunction "1_1") (pintype "passive"))
      (node (ref "R97") (pin "2") (pinfunction "2_2") (pintype "passive"))
    )
    (net (code "16") (name "Net-(D1-A)") (class "Default")
      (node (ref "C79") (pin "2") (pinfunction "2_2") (pintype "passive"))
      (node (ref "D1") (pin "1") (pinfunction "A_1") (pintype "passive"))
      (node (ref "Q1") (pin "3") (pinfunction "G_3") (pintype "passive"))
      (node (ref "Q2") (pin "3") (pinfunction "G_3") (pintype "passive"))
      (node (ref "Q9") (pin "3") (pinfunction "C_3") (pintype "passive"))
      (node (ref "R36") (pin "2") (pinfunction "2_2") (pintype "passive"))
    )
    (net (code "17") (name "Net-(D1-K)") (class "Default")
      (node (ref "D1") (pin "2") (pinfunction "K_2") (pintype "passive"))
      (node (ref "Q1") (pin "1") (pinfunction "D_1") (pintype "passive"))
      (node (ref "Q1") (pin "2") (pinfunction "D_2") (pintype "passive"))
      (node (ref "Q1") (pin "5") (pinfunction "D_5") (pintype "passive"))
      (node (ref "Q1") (pin "6") (pinfunction "D_6") (pintype "passive"))
      (node (ref "Q9") (pin "2") (pinfunction "E_2") (pintype "passive"))
      (node (ref "R7") (pin "2") (pinfunction "2_2") (pintype "passive"))
    )
    (net (code "18") (name "Net-(D2-A)") (class "Default")
      (node (ref "C44") (pin "1") (pinfunction "1_1") (pintype "passive"))
      (node (ref "D2") (pin "2") (pinfunction "A_2") (pintype "passive"))
      (node (ref "L3") (pin "4") (pinfunction "4_4") (pintype "passive"))
    )
    (net (code "19") (name "Net-(D11-A)") (class "Default")
      (node (ref "D11") (pin "1") (pinfunction "A_1") (pintype "passive"))
      (node (ref "L5") (pin "2") (pinfunction "2_2") (pintype "passive"))
      (node (ref "Q7") (pin "5") (pinfunction "D_5") (pintype "passive"))
      (node (ref "Q7") (pin "6") (pinfunction "D_6") (pintype "passive"))
      (node (ref "Q7") (pin "7") (pinfunction "D_7") (pintype "passive"))
      (node (ref "Q7") (pin "8") (pinfunction "D_8") (pintype "passive"))
      (node (ref "Q7") (pin "9") (pinfunction "D_9") (pintype "passive"))
    )
    (net (code "20") (name "Net-(D12-A)") (class "Default")
      (node (ref "D12") (pin "1") (pinfunction "A_1") (pintype "passive"))
      (node (ref "R106") (pin "1") (pinfunction "1_1") (pintype "passive"))
      (node (ref "U9") (pin "12") (pinfunction "CS_12") (pintype "passive"))
    )
    (net (code "21") (name "Net-(D12-K)") (class "Default")
      (node (ref "C86") (pin "2") (pinfunction "2_2") (pintype "passive"))
      (node (ref "D12") (pin "2") (pinfunction "K_2") (pintype "passive"))
      (node (ref "L5") (pin "1") (pinfunction "1_1") (pintype "passive"))
      (node (ref "Q6") (pin "1") (pinfunction "S_1") (pintype "passive"))
      (node (ref "Q6") (pin "2") (pinfunction "S_2") (pintype "passive"))
      (node (ref "Q6") (pin "3") (pinfunction "S_3") (pintype "passive"))
      (node (ref "U9") (pin "20") (pinfunction "HS_20") (pintype "passive"))
    )
    (net (code "22") (name "Net-(FB3-Pad1)") (class "Default")
      (node (ref "FB3") (pin "1") (pinfunction "1_1") (pintype "passive"))
      (node (ref "Q2") (pin "1") (pinfunction "D_1") (pintype "passive"))
      (node (ref "Q2") (pin "2") (pinfunction "D_2") (pintype "passive"))
      (node (ref "Q2") (pin "5") (pinfunction "D_5") (pintype "passive"))
      (node (ref "Q2") (pin "6") (pinfunction "D_6") (pintype "passive"))
    )
    (net (code "23") (name "Net-(Q1-S)") (class "Default")
      (node (ref "C79") (pin "1") (pinfunction "1_1") (pintype "passive"))
      (node (ref "L4") (pin "4") (pinfunction "4_4") (pintype "passive"))
      (node (ref "Q1") (pin "4") (pinfunction "S_4") (pintype "passive"))
    )
    (net (code "24") (name "Net-(Q2-S)") (class "Default")
      (node (ref "Q2") (pin "4") (pinfunction "S_4") (pintype "passive"))
      (node (ref "R35") (pin "1") (pinfunction "1_1") (pintype "passive"))
      (node (ref "R7") (pin "1") (pinfunction "1_1") (pintype "passive"))
    )
    (net (code "25") (name "Net-(Q6-G)") (class "Default")
      (node (ref "Q6") (pin "4") (pinfunction "G_4") (pintype "passive"))
      (node (ref "U9") (pin "19") (pinfunction "HO_19") (pintype "passive"))
    )
    (net (code "26") (name "Net-(Q7-G)") (class "Default")
      (node (ref "Q7") (pin "4") (pinfunction "G_4") (pintype "passive"))
      (node (ref "U9") (pin "15") (pinfunction "LO_15") (pintype "passive"))
    )
    (net (code "27") (name "Net-(Q9-B)") (class "Default")
      (node (ref "Q9") (pin "1") (pinfunction "B_1") (pintype "passive"))
      (node (ref "R35") (pin "2") (pinfunction "2_2") (pintype "passive"))
    )
    (net (code "28") (name "Net-(U9-COMP)") (class "Default")
      (node (ref "C134") (pin "1") (pinfunction "1_1") (pintype "passive"))
      (node (ref "R97") (pin "1") (pinfunction "1_1") (pintype "passive"))
      (node (ref "U9") (pin "9") (pinfunction "COMP_9") (pintype "passive"))
    )
    (net (code "29") (name "Net-(U9-EN)") (class "Default")
      (node (ref "R25") (pin "2") (pinfunction "2_2") (pintype "passive"))
      (node (ref "U9") (pin "4") (pinfunction "EN_4") (pintype "passive"))
    )
    (net (code "30") (name "Net-(U9-FB)") (class "Default")
      (node (ref "C134") (pin "2") (pinfunction "2_2") (pintype "passive"))
      (node (ref "C140") (pin "2") (pinfunction "2_2") (pintype "passive"))
      (node (ref "R107") (pin "1") (pinfunction "1_1") (pintype "passive"))
      (node (ref "R108") (pin "2") (pinfunction "2_2") (pintype "passive"))
      (node (ref "U9") (pin "8") (pinfunction "FB_8") (pintype "passive"))
    )
    (net (code "31") (name "Net-(U9-HB)") (class "Default")
      (node (ref "C86") (pin "1") (pinfunction "1_1") (pintype "passive"))
      (node (ref "U9") (pin "18") (pinfunction "HB_18") (pintype "passive"))
    )
    (net (code "32") (name "Net-(U9-RAMP)") (class "Default")
      (node (ref "C132") (pin "1") (pinfunction "1_1") (pintype "passive"))
      (node (ref "R54") (pin "2") (pinfunction "2_2") (pintype "passive"))
      (node (ref "U9") (pin "5") (pinfunction "RAMP_5") (pintype "passive"))
    )
    (net (code "33") (name "Net-(U9-RT)") (class "Default")
      (node (ref "R50") (pin "1") (pinfunction "1_1") (pintype "passive"))
      (node (ref "U9") (pin "3") (pinfunction "RT_3") (pintype "passive"))
    )
    (net (code "34") (name "Net-(U9-SS)") (class "Default")
      (node (ref "C133") (pin "1") (pinfunction "1_1") (pintype "passive"))
      (node (ref "U9") (pin "7") (pinfunction "SS_7") (pintype "passive"))
    )
    (net (code "35") (name "Net-(U9-UVLO)") (class "Default")
      (node (ref "R33") (pin "2") (pinfunction "2_2") (pintype "passive"))
      (node (ref "R55") (pin "1") (pinfunction "1_1") (pintype "passive"))
      (node (ref "U9") (pin "2") (pinfunction "UVLO_2") (pintype "passive"))
    )
    (net (code "36") (name "Net-(U10-EN)") (class "Default")
      (node (ref "C71") (pin "1") (pinfunction "1_1") (pintype "passive"))
      (node (ref "FB4") (pin "2") (pinfunction "2_2") (pintype "passive"))
      (node (ref "U10") (pin "3") (pinfunction "VIN_3") (pintype "power_in"))
      (node (ref "U10") (pin "5") (pinfunction "EN_5") (pintype "input"))
    )
    (net (code "37") (name "Net-(U10-SW)") (class "Default")
      (node (ref "C70") (pin "2") (pinfunction "2_2") (pintype "passive"))
      (node (ref "L1") (pin "1") (pinfunction "1_1") (pintype "passive"))
      (node (ref "U10") (pin "2") (pinfunction "SW_2") (pintype "output"))
    )
    (net (code "38") (name "Net-(U10-VBST)") (class "Default")
      (node (ref "C70") (pin "1") (pinfunction "1_1") (pintype "passive"))
      (node (ref "U10") (pin "6") (pinfunction "VBST_6") (pintype "input"))
    )
    (net (code "39") (name "Net-(U10-VFB)") (class "Default")
      (node (ref "C73") (pin "2") (pinfunction "2_2") (pintype "passive"))
      (node (ref "R8") (pin "1") (pinfunction "1_1") (pintype "passive"))
      (node (ref "R9") (pin "2") (pinfunction "2_2") (pintype "passive"))
      (node (ref "U10") (pin "4") (pinfunction "VFB_4") (pintype "input"))
    )
    (net (code "40") (name "Net-(U11-BOOT)") (class "Default")
      (node (ref "C25") (pin "1") (pinfunction "1_1") (pintype "passive"))
      (node (ref "U11") (pin "7") (pinfunction "BOOT_7") (pintype "passive"))
    )
    (net (code "41") (name "Net-(U11-EN)") (class "Default")
      (node (ref "C41") (pin "1") (pinfunction "1_1") (pintype "passive"))
      (node (ref "FB11") (pin "2") (pinfunction "2_2") (pintype "passive"))
      (node (ref "U11") (pin "2") (pinfunction "VIN_2") (pintype "passive"))
      (node (ref "U11") (pin "3") (pinfunction "EN_3") (pintype "input"))
    )
    (net (code "42") (name "Net-(U11-FB)") (class "Default")
      (node (ref "C45") (pin "2") (pinfunction "2_2") (pintype "passive"))
      (node (ref "R30") (pin "2") (pinfunction "2_2") (pintype "passive"))
      (node (ref "R98") (pin "1") (pinfunction "1_1") (pintype "passive"))
      (node (ref "U11") (pin "5") (pinfunction "FB_5") (pintype "passive"))
    )
    (net (code "43") (name "Net-(U11-SW)") (class "Default")
      (node (ref "C25") (pin "2") (pinfunction "2_2") (pintype "passive"))
      (node (ref "L3") (pin "1") (pinfunction "1_1") (pintype "passive"))
      (node (ref "U11") (pin "8") (pinfunction "SW_8") (pintype "passive"))
    )
    (net (code "44") (name "Net-(U11-VCC)") (class "Default")
      (node (ref "C68") (pin "1") (pinfunction "1_1") (pintype "passive"))
      (node (ref "U11") (pin "6") (pinfunction "VCC_6") (pintype "passive"))
    )
    (net (code "45") (name "Net-(U12-VOUT)") (class "Default")
      (node (ref "C50") (pin "1") (pinfunction "1_1") (pintype "passive"))
      (node (ref "FB5") (pin "1") (pinfunction "1_1") (pintype "passive"))
      (node (ref "U12") (pin "5") (pinfunction "VOUT_5") (pintype "passive"))
    )
    (net (code "46") (name "V_Power") (class "Default")
      (node (ref "F5") (pin "2") (pinfunction "2_2") (pintype "passive"))
      (node (ref "FB11") (pin "1") (pinfunction "1_1") (pintype "passive"))
    )
    (net (code "47") (name "V_Power_F") (class "Default")
      (node (ref "C27") (pin "1") (pinfunction "1_1") (pintype "passive"))
      (node (ref "C60") (pin "1") (pinfunction "1_1") (pintype "passive"))
      (node (ref "C62") (pin "1") (pinfunction "1_1") (pintype "passive"))
      (node (ref "C80") (pin "1") (pinfunction "1_1") (pintype "passive"))
      (node (ref "C83") (pin "1") (pinfunction "1_1") (pintype "passive"))
      (node (ref "C84") (pin "1") (pinfunction "1_1") (pintype "passive"))
      (node (ref "C85") (pin "1") (pinfunction "1_1") (pintype "passive"))
      (node (ref "D9") (pin "2") (pinfunction "A_2") (pintype "passive"))
      (node (ref "F5") (pin "1") (pinfunction "1_1") (pintype "passive"))
      (node (ref "FB3") (pin "2") (pinfunction "2_2") (pintype "passive"))
      (node (ref "Q6") (pin "5") (pinfunction "D_5") (pintype "passive"))
      (node (ref "R109") (pin "2") (pinfunction "2_2") (pintype "passive"))
      (node (ref "R25") (pin "1") (pinfunction "1_1") (pintype "passive"))
      (node (ref "R28") (pin "2") (pinfunction "2_2") (pintype "passive"))
      (node (ref "R33") (pin "1") (pinfunction "1_1") (pintype "passive"))
      (node (ref "U9") (pin "1") (pinfunction "VIN_1") (pintype "passive"))
    )
    (net (code "48") (name "Vin") (class "Default")
      (node (ref "C31") (pin "1") (pinfunction "1_1") (pintype "passive"))
      (node (ref "C59") (pin "1") (pinfunction "1_1") (pintype "passive"))
      (node (ref "L4") (pin "1") (pinfunction "1_1") (pintype "passive"))
    )
    (net (code "49") (name "Vin_RTN") (class "Default")
      (node (ref "C24") (pin "1") (pinfunction "1_1") (pintype "passive"))
      (node (ref "C31") (pin "2") (pinfunction "2_2") (pintype "passive"))
      (node (ref "L4") (pin "2") (pinfunction "2_2") (pintype "passive"))
    )
    (net (code "50") (name "unconnected-(U9-SYNC-Pad11)") (class "Default")
      (node (ref "U9") (pin "11") (pinfunction "SYNC_11") (pintype "passive"))
    )
    (net (code "51") (name "unconnected-(U11-PG-Pad4)") (class "Default")
      (node (ref "U11") (pin "4") (pinfunction "PG_4") (pintype "passive"))
    )
    (net (code "52") (name "unconnected-(U12-NC-Pad4)") (class "Default")
      (node (ref "U12") (pin "4") (pinfunction "NC_4") (pintype "passive"))
    )
  )
)
